# tm7_revD.net
KiCad netlist of a schematic drawn in EAGLE
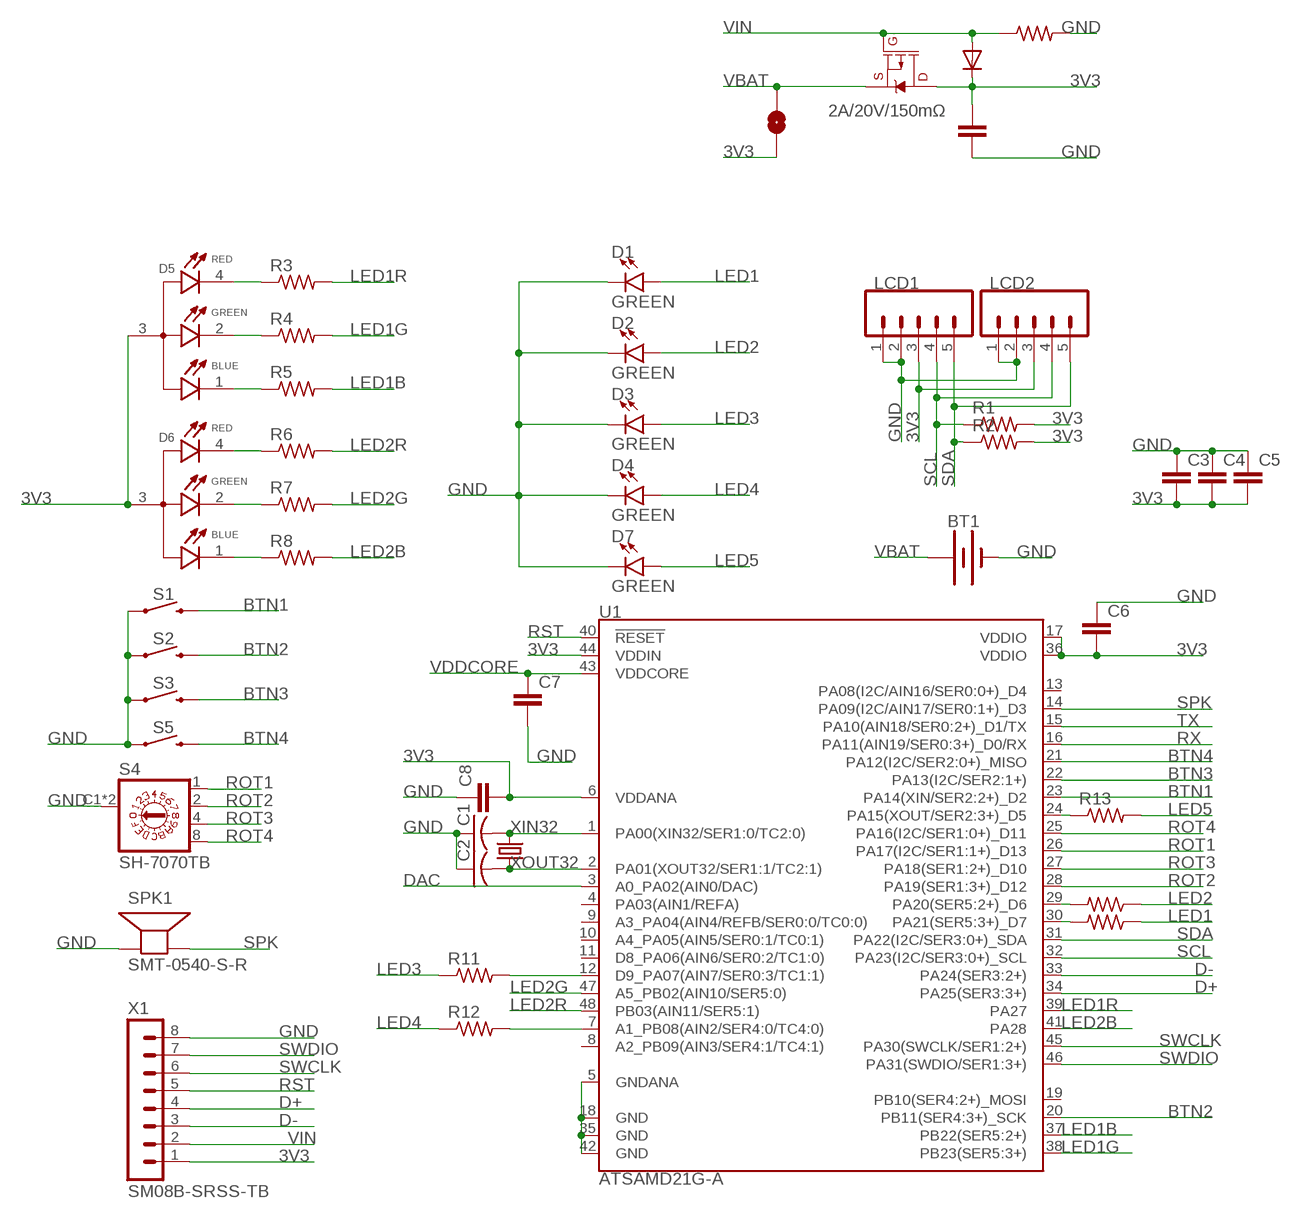
[diagram p0: schematic, sheet 1]

(export (version "E")
  (design (tool "Eeschema 10.0.6"))
  (components
    (comp (ref "BT1")
      (value "BATTERY-20MM_SMD_4LEGS_OVERPASTE_INNER")
      (footprint "eagle-import:BATTCON_20MM_4LEGS_OVERPASTE_INNER")
      (libsource (lib "eagle-import") (part "BATTERY-20MM_SMD_4LEGS_OVERPASTE_INNER"))
    )
    (comp (ref "C1")
      (value "C-USC0603")
      (footprint "eagle-import:C0603")
      (libsource (lib "eagle-import") (part "C-USC0603"))
    )
    (comp (ref "C2")
      (value "C-USC0603")
      (footprint "eagle-import:C0603")
      (libsource (lib "eagle-import") (part "C-USC0603"))
    )
    (comp (ref "C3")
      (value "C-EUC0603")
      (footprint "eagle-import:C0603")
      (libsource (lib "eagle-import") (part "C-EUC0603"))
    )
    (comp (ref "C4")
      (value "C-EUC0603")
      (footprint "eagle-import:C0603")
      (libsource (lib "eagle-import") (part "C-EUC0603"))
    )
    (comp (ref "C5")
      (value "C-EUC0603")
      (footprint "eagle-import:C0603")
      (libsource (lib "eagle-import") (part "C-EUC0603"))
    )
    (comp (ref "C6")
      (value "C-EUC0603")
      (footprint "eagle-import:C0603")
      (libsource (lib "eagle-import") (part "C-EUC0603"))
    )
    (comp (ref "C7")
      (value "C-EUC0603")
      (footprint "eagle-import:C0603")
      (libsource (lib "eagle-import") (part "C-EUC0603"))
    )
    (comp (ref "C8")
      (value "C-EUC0603")
      (footprint "eagle-import:C0603")
      (libsource (lib "eagle-import") (part "C-EUC0603"))
    )
    (comp (ref "C9")
      (value "C-EUC0603")
      (footprint "eagle-import:C0603")
      (libsource (lib "eagle-import") (part "C-EUC0603"))
    )
    (comp (ref "D1")
      (value "GREEN")
      (footprint "eagle-import:LED-1206")
      (libsource (lib "eagle-import") (part "LED-GREEN1206"))
    )
    (comp (ref "D2")
      (value "GREEN")
      (footprint "eagle-import:LED-1206")
      (libsource (lib "eagle-import") (part "LED-GREEN1206"))
    )
    (comp (ref "D3")
      (value "GREEN")
      (footprint "eagle-import:LED-1206")
      (libsource (lib "eagle-import") (part "LED-GREEN1206"))
    )
    (comp (ref "D4")
      (value "GREEN")
      (footprint "eagle-import:LED-1206")
      (libsource (lib "eagle-import") (part "LED-GREEN1206"))
    )
    (comp (ref "D5")
      (value "EAST1616RGBA3")
      (footprint "eagle-import:LED_EAST1616RGBA3")
      (fields (field (name "MF") "Everlight Electronics"))
      (libsource (lib "eagle-import") (part "EAST1616RGBA3"))
    )
    (comp (ref "D6")
      (value "EAST1616RGBA3")
      (footprint "eagle-import:LED_EAST1616RGBA3")
      (fields (field (name "MF") "Everlight Electronics"))
      (libsource (lib "eagle-import") (part "EAST1616RGBA3"))
    )
    (comp (ref "D7")
      (value "GREEN")
      (footprint "eagle-import:LED-1206")
      (libsource (lib "eagle-import") (part "LED-GREEN1206"))
    )
    (comp (ref "D8")
      (value "DIODESOD-323F")
      (footprint "eagle-import:SOD-323F")
      (libsource (lib "eagle-import") (part "DIODESOD-323F"))
    )
    (comp (ref "JP1")
      (value "JUMPER-SMT_2_NO_NO-SILK")
      (footprint "eagle-import:SMT-JUMPER_2_NO_NO-SILK")
      (libsource (lib "eagle-import") (part "JUMPER-SMT_2_NO_NO-SILK"))
    )
    (comp (ref "LCD1")
      (value "CONN_05VERT_FEMALE_HEADER")
      (footprint "eagle-import:1X05_SMD_VERTICAL_COMBO")
      (libsource (lib "eagle-import") (part "CONN_05VERT_FEMALE_HEADER"))
    )
    (comp (ref "LCD2")
      (value "CONN_05VERT_FEMALE_HEADER")
      (footprint "eagle-import:1X05_SMD_VERTICAL_COMBO")
      (libsource (lib "eagle-import") (part "CONN_05VERT_FEMALE_HEADER"))
    )
    (comp (ref "Q1")
      (value "2A/20V/150mΩ")
      (footprint "eagle-import:SOT26")
      (libsource (lib "eagle-import") (part "MOSFET_PCH_DUAL-DMP2240UDM"))
    )
    (comp (ref "R1")
      (value "R-US_R0603")
      (footprint "eagle-import:R0603")
      (libsource (lib "eagle-import") (part "rcl_334_R-US_R0603"))
    )
    (comp (ref "R2")
      (value "R-US_R0603")
      (footprint "eagle-import:R0603")
      (libsource (lib "eagle-import") (part "rcl_334_R-US_R0603"))
    )
    (comp (ref "R3")
      (value "R-US_R0603")
      (footprint "eagle-import:R0603")
      (libsource (lib "eagle-import") (part "rcl_334_R-US_R0603"))
    )
    (comp (ref "R4")
      (value "R-US_R0603")
      (footprint "eagle-import:R0603")
      (libsource (lib "eagle-import") (part "rcl_334_R-US_R0603"))
    )
    (comp (ref "R5")
      (value "R-US_R0603")
      (footprint "eagle-import:R0603")
      (libsource (lib "eagle-import") (part "rcl_334_R-US_R0603"))
    )
    (comp (ref "R6")
      (value "R-US_R0603")
      (footprint "eagle-import:R0603")
      (libsource (lib "eagle-import") (part "rcl_334_R-US_R0603"))
    )
    (comp (ref "R7")
      (value "R-US_R0603")
      (footprint "eagle-import:R0603")
      (libsource (lib "eagle-import") (part "rcl_334_R-US_R0603"))
    )
    (comp (ref "R8")
      (value "R-US_R0603")
      (footprint "eagle-import:R0603")
      (libsource (lib "eagle-import") (part "rcl_334_R-US_R0603"))
    )
    (comp (ref "R9")
      (value "R-US_R0603")
      (footprint "eagle-import:R0603")
      (libsource (lib "eagle-import") (part "rcl_334_R-US_R0603"))
    )
    (comp (ref "R10")
      (value "R-US_R0603")
      (footprint "eagle-import:R0603")
      (libsource (lib "eagle-import") (part "rcl_334_R-US_R0603"))
    )
    (comp (ref "R11")
      (value "R-US_R0603")
      (footprint "eagle-import:R0603")
      (libsource (lib "eagle-import") (part "rcl_334_R-US_R0603"))
    )
    (comp (ref "R12")
      (value "R-US_R0603")
      (footprint "eagle-import:R0603")
      (libsource (lib "eagle-import") (part "rcl_334_R-US_R0603"))
    )
    (comp (ref "R13")
      (value "R-US_R0603")
      (footprint "eagle-import:R0603")
      (libsource (lib "eagle-import") (part "rcl_334_R-US_R0603"))
    )
    (comp (ref "R14")
      (value "R-US_R0603")
      (footprint "eagle-import:R0603")
      (libsource (lib "eagle-import") (part "R-US_R0603"))
    )
    (comp (ref "S1")
      (value "MOMENTARY-SWITCH-SPST-SMD-6.0X3.5MM")
      (footprint "eagle-import:TACTILE_SWITCH_SMD_6.0X3.5MM")
      (libsource (lib "eagle-import") (part "MOMENTARY-SWITCH-SPST-SMD-6.0X3.5MM"))
    )
    (comp (ref "S2")
      (value "MOMENTARY-SWITCH-SPST-SMD-6.0X3.5MM")
      (footprint "eagle-import:TACTILE_SWITCH_SMD_6.0X3.5MM")
      (libsource (lib "eagle-import") (part "MOMENTARY-SWITCH-SPST-SMD-6.0X3.5MM"))
    )
    (comp (ref "S3")
      (value "MOMENTARY-SWITCH-SPST-SMD-6.0X3.5MM")
      (footprint "eagle-import:TACTILE_SWITCH_SMD_6.0X3.5MM")
      (libsource (lib "eagle-import") (part "MOMENTARY-SWITCH-SPST-SMD-6.0X3.5MM"))
    )
    (comp (ref "S4")
      (value "SH-7070TB")
      (footprint "eagle-import:SH-7070B")
      (fields (field (name "MF") "Nidec Copal"))
      (libsource (lib "eagle-import") (part "SH-7070TB"))
    )
    (comp (ref "S5")
      (value "MOMENTARY-SWITCH-SPST-SMD-6.0X3.5MM")
      (footprint "eagle-import:TACTILE_SWITCH_SMD_6.0X3.5MM")
      (libsource (lib "eagle-import") (part "MOMENTARY-SWITCH-SPST-SMD-6.0X3.5MM"))
    )
    (comp (ref "SPK1")
      (value "SMT-0540-S-R")
      (footprint "eagle-import:SMT-0540-S-R")
      (fields (field (name "MF") "PUI"))
      (libsource (lib "eagle-import") (part "SMT-0540-S-R"))
    )
    (comp (ref "U1")
      (value "ATSAMD21G-A")
      (footprint "eagle-import:TQFP-48")
      (libsource (lib "eagle-import") (part "ATSAMD21G-A"))
    )
    (comp (ref "X1")
      (value "SM08B-SRSS-TB")
      (footprint "eagle-import:SM08B-SRSS-TB")
      (libsource (lib "eagle-import") (part "SM08B-SRSS-TB"))
    )
    (comp (ref "Y1")
      (value "32.768kHz")
      (footprint "eagle-import:CRYSTAL-SMD-3.2X1.5MM")
      (libsource (lib "eagle-import") (part "CRYSTAL-32.768KHZSMD-3.2X1.5"))
    )
  )
  (nets
    (net (code "1") (name "/3V3") (class "Default")
      (node (ref "C3") (pin "2") (pinfunction "2_2") (pintype "passive"))
      (node (ref "C4") (pin "2") (pinfunction "2_2") (pintype "passive"))
      (node (ref "C5") (pin "2") (pinfunction "2_2") (pintype "passive"))
      (node (ref "C6") (pin "2") (pinfunction "2_2") (pintype "passive"))
      (node (ref "C8") (pin "2") (pinfunction "2_2") (pintype "passive"))
      (node (ref "C9") (pin "1") (pinfunction "1_1") (pintype "passive"))
      (node (ref "D5") (pin "3") (pinfunction "A_3") (pintype "passive"))
      (node (ref "D6") (pin "3") (pinfunction "A_3") (pintype "passive"))
      (node (ref "D8") (pin "C") (pinfunction "C_C") (pintype "passive"))
      (node (ref "JP1") (pin "1") (pinfunction "1_1") (pintype "passive"))
      (node (ref "LCD1") (pin "3") (pinfunction "3_3") (pintype "passive"))
      (node (ref "LCD2") (pin "3") (pinfunction "3_3") (pintype "passive"))
      (node (ref "Q1") (pin "D1") (pinfunction "D_D1") (pintype "bidirectional"))
      (node (ref "R1") (pin "2") (pinfunction "2_2") (pintype "passive"))
      (node (ref "R2") (pin "2") (pinfunction "2_2") (pintype "passive"))
      (node (ref "U1") (pin "17") (pinfunction "VDDIO_17") (pintype "bidirectional"))
      (node (ref "U1") (pin "36") (pinfunction "VDDIO_36") (pintype "bidirectional"))
      (node (ref "U1") (pin "44") (pinfunction "VDDIN_44") (pintype "bidirectional"))
      (node (ref "U1") (pin "6") (pinfunction "VDDANA_6") (pintype "bidirectional"))
      (node (ref "X1") (pin "1") (pinfunction "1_1") (pintype "passive"))
    )
    (net (code "2") (name "/BTN1") (class "Default")
      (node (ref "S1") (pin "2") (pinfunction "2_2") (pintype "passive"))
      (node (ref "U1") (pin "23") (pinfunction "PA14(XIN/SER2:2+)_D2_23") (pintype "bidirectional"))
    )
    (net (code "3") (name "/BTN2") (class "Default")
      (node (ref "S2") (pin "2") (pinfunction "2_2") (pintype "passive"))
      (node (ref "U1") (pin "20") (pinfunction "PB11(SER4:3+)_SCK_20") (pintype "bidirectional"))
    )
    (net (code "4") (name "/BTN3") (class "Default")
      (node (ref "S3") (pin "2") (pinfunction "2_2") (pintype "passive"))
      (node (ref "U1") (pin "22") (pinfunction "PA13(I2C/SER2:1+)_22") (pintype "bidirectional"))
    )
    (net (code "5") (name "/BTN4") (class "Default")
      (node (ref "S5") (pin "2") (pinfunction "2_2") (pintype "passive"))
      (node (ref "U1") (pin "21") (pinfunction "PA12(I2C/SER2:0+)_MISO_21") (pintype "bidirectional"))
    )
    (net (code "6") (name "/D+") (class "Default")
      (node (ref "U1") (pin "34") (pinfunction "PA25(SER3:3+)_34") (pintype "bidirectional"))
      (node (ref "X1") (pin "4") (pinfunction "4_4") (pintype "passive"))
    )
    (net (code "7") (name "/D-") (class "Default")
      (node (ref "U1") (pin "33") (pinfunction "PA24(SER3:2+)_33") (pintype "bidirectional"))
      (node (ref "X1") (pin "3") (pinfunction "3_3") (pintype "passive"))
    )
    (net (code "8") (name "/DAC") (class "Default")
      (node (ref "U1") (pin "3") (pinfunction "A0_PA02(AIN0/DAC)_3") (pintype "bidirectional"))
    )
    (net (code "9") (name "/GND") (class "Default")
      (node (ref "BT1") (pin "2") (pinfunction "-_2") (pintype "power_in"))
      (node (ref "C1") (pin "1") (pinfunction "1_1") (pintype "passive"))
      (node (ref "C2") (pin "1") (pinfunction "1_1") (pintype "passive"))
      (node (ref "C3") (pin "1") (pinfunction "1_1") (pintype "passive"))
      (node (ref "C4") (pin "1") (pinfunction "1_1") (pintype "passive"))
      (node (ref "C5") (pin "1") (pinfunction "1_1") (pintype "passive"))
      (node (ref "C6") (pin "1") (pinfunction "1_1") (pintype "passive"))
      (node (ref "C7") (pin "2") (pinfunction "2_2") (pintype "passive"))
      (node (ref "C8") (pin "1") (pinfunction "1_1") (pintype "passive"))
      (node (ref "C9") (pin "2") (pinfunction "2_2") (pintype "passive"))
      (node (ref "D1") (pin "C") (pinfunction "C_C") (pintype "passive"))
      (node (ref "D2") (pin "C") (pinfunction "C_C") (pintype "passive"))
      (node (ref "D3") (pin "C") (pinfunction "C_C") (pintype "passive"))
      (node (ref "D4") (pin "C") (pinfunction "C_C") (pintype "passive"))
      (node (ref "D7") (pin "C") (pinfunction "C_C") (pintype "passive"))
      (node (ref "LCD1") (pin "1") (pinfunction "1_1") (pintype "passive"))
      (node (ref "LCD1") (pin "2") (pinfunction "2_2") (pintype "passive"))
      (node (ref "LCD2") (pin "1") (pinfunction "1_1") (pintype "passive"))
      (node (ref "LCD2") (pin "2") (pinfunction "2_2") (pintype "passive"))
      (node (ref "R14") (pin "2") (pinfunction "2_2") (pintype "passive"))
      (node (ref "S1") (pin "1") (pinfunction "1_1") (pintype "passive"))
      (node (ref "S2") (pin "1") (pinfunction "1_1") (pintype "passive"))
      (node (ref "S3") (pin "1") (pinfunction "1_1") (pintype "passive"))
      (node (ref "S4") (pin "C1") (pinfunction "C_C1") (pintype "passive"))
      (node (ref "S4") (pin "C2") (pinfunction "C_C2") (pintype "passive"))
      (node (ref "S5") (pin "1") (pinfunction "1_1") (pintype "passive"))
      (node (ref "SPK1") (pin "-") (pinfunction "+_-") (pintype "passive"))
      (node (ref "U1") (pin "18") (pinfunction "GND_18") (pintype "bidirectional"))
      (node (ref "U1") (pin "35") (pinfunction "GND_35") (pintype "bidirectional"))
      (node (ref "U1") (pin "42") (pinfunction "GND_42") (pintype "bidirectional"))
      (node (ref "U1") (pin "5") (pinfunction "GNDANA_5") (pintype "bidirectional"))
      (node (ref "X1") (pin "8") (pinfunction "8_8") (pintype "passive"))
    )
    (net (code "10") (name "/LED1") (class "Default")
      (node (ref "D1") (pin "A") (pinfunction "A_A") (pintype "passive"))
      (node (ref "R9") (pin "1") (pinfunction "1_1") (pintype "passive"))
    )
    (net (code "11") (name "/LED1B") (class "Default")
      (node (ref "R5") (pin "2") (pinfunction "2_2") (pintype "passive"))
      (node (ref "U1") (pin "37") (pinfunction "PB22(SER5:2+)_37") (pintype "bidirectional"))
    )
    (net (code "12") (name "/LED1G") (class "Default")
      (node (ref "R4") (pin "2") (pinfunction "2_2") (pintype "passive"))
      (node (ref "U1") (pin "38") (pinfunction "PB23(SER5:3+)_38") (pintype "bidirectional"))
    )
    (net (code "13") (name "/LED1R") (class "Default")
      (node (ref "R3") (pin "2") (pinfunction "2_2") (pintype "passive"))
      (node (ref "U1") (pin "39") (pinfunction "PA27_39") (pintype "bidirectional"))
    )
    (net (code "14") (name "/LED2") (class "Default")
      (node (ref "D2") (pin "A") (pinfunction "A_A") (pintype "passive"))
      (node (ref "R10") (pin "1") (pinfunction "1_1") (pintype "passive"))
    )
    (net (code "15") (name "/LED2B") (class "Default")
      (node (ref "R8") (pin "2") (pinfunction "2_2") (pintype "passive"))
      (node (ref "U1") (pin "41") (pinfunction "PA28_41") (pintype "bidirectional"))
    )
    (net (code "16") (name "/LED2G") (class "Default")
      (node (ref "R7") (pin "2") (pinfunction "2_2") (pintype "passive"))
      (node (ref "U1") (pin "47") (pinfunction "A5_PB02(AIN10/SER5:0)_47") (pintype "bidirectional"))
    )
    (net (code "17") (name "/LED2R") (class "Default")
      (node (ref "R6") (pin "2") (pinfunction "2_2") (pintype "passive"))
      (node (ref "U1") (pin "48") (pinfunction "PB03(AIN11/SER5:1)_48") (pintype "bidirectional"))
    )
    (net (code "18") (name "/LED3") (class "Default")
      (node (ref "D3") (pin "A") (pinfunction "A_A") (pintype "passive"))
      (node (ref "R11") (pin "1") (pinfunction "1_1") (pintype "passive"))
    )
    (net (code "19") (name "/LED4") (class "Default")
      (node (ref "D4") (pin "A") (pinfunction "A_A") (pintype "passive"))
      (node (ref "R12") (pin "1") (pinfunction "1_1") (pintype "passive"))
    )
    (net (code "20") (name "/LED5") (class "Default")
      (node (ref "D7") (pin "A") (pinfunction "A_A") (pintype "passive"))
      (node (ref "R13") (pin "2") (pinfunction "2_2") (pintype "passive"))
    )
    (net (code "21") (name "/ROT1") (class "Default")
      (node (ref "S4") (pin "1") (pinfunction "1_1") (pintype "passive"))
      (node (ref "U1") (pin "26") (pinfunction "PA17(I2C/SER1:1+)_D13_26") (pintype "bidirectional"))
    )
    (net (code "22") (name "/ROT2") (class "Default")
      (node (ref "S4") (pin "2") (pinfunction "2_2") (pintype "passive"))
      (node (ref "U1") (pin "28") (pinfunction "PA19(SER1:3+)_D12_28") (pintype "bidirectional"))
    )
    (net (code "23") (name "/ROT3") (class "Default")
      (node (ref "S4") (pin "4") (pinfunction "4_4") (pintype "passive"))
      (node (ref "U1") (pin "27") (pinfunction "PA18(SER1:2+)_D10_27") (pintype "bidirectional"))
    )
    (net (code "24") (name "/ROT4") (class "Default")
      (node (ref "S4") (pin "8") (pinfunction "8_8") (pintype "passive"))
      (node (ref "U1") (pin "25") (pinfunction "PA16(I2C/SER1:0+)_D11_25") (pintype "bidirectional"))
    )
    (net (code "25") (name "/RST") (class "Default")
      (node (ref "U1") (pin "40") (pinfunction "~{RESET}_40") (pintype "bidirectional"))
      (node (ref "X1") (pin "5") (pinfunction "5_5") (pintype "passive"))
    )
    (net (code "26") (name "/RX") (class "Default")
      (node (ref "U1") (pin "16") (pinfunction "PA11(AIN19/SER0:3+)_D0/RX_16") (pintype "bidirectional"))
    )
    (net (code "27") (name "/SCL") (class "Default")
      (node (ref "LCD1") (pin "4") (pinfunction "4_4") (pintype "passive"))
      (node (ref "LCD2") (pin "4") (pinfunction "4_4") (pintype "passive"))
      (node (ref "R1") (pin "1") (pinfunction "1_1") (pintype "passive"))
      (node (ref "U1") (pin "32") (pinfunction "PA23(I2C/SER3:0+)_SCL_32") (pintype "bidirectional"))
    )
    (net (code "28") (name "/SDA") (class "Default")
      (node (ref "LCD1") (pin "5") (pinfunction "5_5") (pintype "passive"))
      (node (ref "LCD2") (pin "5") (pinfunction "5_5") (pintype "passive"))
      (node (ref "R2") (pin "1") (pinfunction "1_1") (pintype "passive"))
      (node (ref "U1") (pin "31") (pinfunction "PA22(I2C/SER3:0+)_SDA_31") (pintype "bidirectional"))
    )
    (net (code "29") (name "/SPK") (class "Default")
      (node (ref "SPK1") (pin "+") (pinfunction "-_+") (pintype "passive"))
      (node (ref "U1") (pin "14") (pinfunction "PA09(I2C/AIN17/SER0:1+)_D3_14") (pintype "bidirectional"))
    )
    (net (code "30") (name "/SWCLK") (class "Default")
      (node (ref "U1") (pin "45") (pinfunction "PA30(SWCLK/SER1:2+)_45") (pintype "bidirectional"))
      (node (ref "X1") (pin "6") (pinfunction "6_6") (pintype "passive"))
    )
    (net (code "31") (name "/SWDIO") (class "Default")
      (node (ref "U1") (pin "46") (pinfunction "PA31(SWDIO/SER1:3+)_46") (pintype "bidirectional"))
      (node (ref "X1") (pin "7") (pinfunction "7_7") (pintype "passive"))
    )
    (net (code "32") (name "/TX") (class "Default")
      (node (ref "U1") (pin "15") (pinfunction "PA10(AIN18/SER0:2+)_D1/TX_15") (pintype "bidirectional"))
    )
    (net (code "33") (name "/VBAT") (class "Default")
      (node (ref "BT1") (pin "1") (pinfunction "+_1") (pintype "power_in"))
      (node (ref "JP1") (pin "2") (pinfunction "2_2") (pintype "passive"))
      (node (ref "Q1") (pin "S1") (pinfunction "S_S1") (pintype "bidirectional"))
    )
    (net (code "34") (name "/VDDCORE") (class "Default")
      (node (ref "C7") (pin "1") (pinfunction "1_1") (pintype "passive"))
      (node (ref "U1") (pin "43") (pinfunction "VDDCORE_43") (pintype "bidirectional"))
    )
    (net (code "35") (name "/VIN") (class "Default")
      (node (ref "D8") (pin "A") (pinfunction "A_A") (pintype "passive"))
      (node (ref "Q1") (pin "G1") (pinfunction "G_G1") (pintype "bidirectional"))
      (node (ref "R14") (pin "1") (pinfunction "1_1") (pintype "passive"))
      (node (ref "X1") (pin "2") (pinfunction "2_2") (pintype "passive"))
    )
    (net (code "36") (name "/XIN32") (class "Default")
      (node (ref "C1") (pin "2") (pinfunction "2_2") (pintype "passive"))
      (node (ref "U1") (pin "1") (pinfunction "PA00(XIN32/SER1:0/TC2:0)_1") (pintype "bidirectional"))
      (node (ref "Y1") (pin "P$2") (pinfunction "2_P$2") (pintype "passive"))
    )
    (net (code "37") (name "/XOUT32") (class "Default")
      (node (ref "C2") (pin "2") (pinfunction "2_2") (pintype "passive"))
      (node (ref "U1") (pin "2") (pinfunction "PA01(XOUT32/SER1:1/TC2:1)_2") (pintype "bidirectional"))
      (node (ref "Y1") (pin "P$1") (pinfunction "1_P$1") (pintype "passive"))
    )
    (net (code "38") (name "Net-(D5-B_C)") (class "Default")
      (node (ref "D5") (pin "1") (pinfunction "B_C_1") (pintype "passive"))
      (node (ref "R5") (pin "1") (pinfunction "1_1") (pintype "passive"))
    )
    (net (code "39") (name "Net-(D5-G_C)") (class "Default")
      (node (ref "D5") (pin "2") (pinfunction "G_C_2") (pintype "passive"))
      (node (ref "R4") (pin "1") (pinfunction "1_1") (pintype "passive"))
    )
    (net (code "40") (name "Net-(D5-R_C)") (class "Default")
      (node (ref "D5") (pin "4") (pinfunction "R_C_4") (pintype "passive"))
      (node (ref "R3") (pin "1") (pinfunction "1_1") (pintype "passive"))
    )
    (net (code "41") (name "Net-(D6-B_C)") (class "Default")
      (node (ref "D6") (pin "1") (pinfunction "B_C_1") (pintype "passive"))
      (node (ref "R8") (pin "1") (pinfunction "1_1") (pintype "passive"))
    )
    (net (code "42") (name "Net-(D6-G_C)") (class "Default")
      (node (ref "D6") (pin "2") (pinfunction "G_C_2") (pintype "passive"))
      (node (ref "R7") (pin "1") (pinfunction "1_1") (pintype "passive"))
    )
    (net (code "43") (name "Net-(D6-R_C)") (class "Default")
      (node (ref "D6") (pin "4") (pinfunction "R_C_4") (pintype "passive"))
      (node (ref "R6") (pin "1") (pinfunction "1_1") (pintype "passive"))
    )
    (net (code "44") (name "Net-(U1-A1_PB08(AIN2{slash}SER4:0{slash}TC4:0))") (class "Default")
      (node (ref "R12") (pin "2") (pinfunction "2_2") (pintype "passive"))
      (node (ref "U1") (pin "7") (pinfunction "A1_PB08(AIN2/SER4:0/TC4:0)_7") (pintype "bidirectional"))
    )
    (net (code "45") (name "Net-(U1-D9_PA07(AIN7{slash}SER0:3{slash}TC1:1))") (class "Default")
      (node (ref "R11") (pin "2") (pinfunction "2_2") (pintype "passive"))
      (node (ref "U1") (pin "12") (pinfunction "D9_PA07(AIN7/SER0:3/TC1:1)_12") (pintype "bidirectional"))
    )
    (net (code "46") (name "Net-(U1-PA15(XOUT{slash}SER2:3+)_D5)") (class "Default")
      (node (ref "R13") (pin "1") (pinfunction "1_1") (pintype "passive"))
      (node (ref "U1") (pin "24") (pinfunction "PA15(XOUT/SER2:3+)_D5_24") (pintype "bidirectional"))
    )
    (net (code "47") (name "Net-(U1-PA20(SER5:2+)_D6)") (class "Default")
      (node (ref "R10") (pin "2") (pinfunction "2_2") (pintype "passive"))
      (node (ref "U1") (pin "29") (pinfunction "PA20(SER5:2+)_D6_29") (pintype "bidirectional"))
    )
    (net (code "48") (name "Net-(U1-PA21(SER5:3+)_D7)") (class "Default")
      (node (ref "R9") (pin "2") (pinfunction "2_2") (pintype "passive"))
      (node (ref "U1") (pin "30") (pinfunction "PA21(SER5:3+)_D7_30") (pintype "bidirectional"))
    )
    (net (code "49") (name "unconnected-(U1-A2_PB09(AIN3{slash}SER4:1{slash}TC4:1)-Pad8)") (class "Default")
      (node (ref "U1") (pin "8") (pinfunction "A2_PB09(AIN3/SER4:1/TC4:1)_8") (pintype "bidirectional"))
    )
    (net (code "50") (name "unconnected-(U1-A3_PA04(AIN4{slash}REFB{slash}SER0:0{slash}TC0:0)-Pad9)") (class "Default")
      (node (ref "U1") (pin "9") (pinfunction "A3_PA04(AIN4/REFB/SER0:0/TC0:0)_9") (pintype "bidirectional"))
    )
    (net (code "51") (name "unconnected-(U1-A4_PA05(AIN5{slash}SER0:1{slash}TC0:1)-Pad10)") (class "Default")
      (node (ref "U1") (pin "10") (pinfunction "A4_PA05(AIN5/SER0:1/TC0:1)_10") (pintype "bidirectional"))
    )
    (net (code "52") (name "unconnected-(U1-D8_PA06(AIN6{slash}SER0:2{slash}TC1:0)-Pad11)") (class "Default")
      (node (ref "U1") (pin "11") (pinfunction "D8_PA06(AIN6/SER0:2/TC1:0)_11") (pintype "bidirectional"))
    )
    (net (code "53") (name "unconnected-(U1-PA03(AIN1{slash}REFA)-Pad4)") (class "Default")
      (node (ref "U1") (pin "4") (pinfunction "PA03(AIN1/REFA)_4") (pintype "bidirectional"))
    )
    (net (code "54") (name "unconnected-(U1-PA08(I2C{slash}AIN16{slash}SER0:0+)_D4-Pad13)") (class "Default")
      (node (ref "U1") (pin "13") (pinfunction "PA08(I2C/AIN16/SER0:0+)_D4_13") (pintype "bidirectional"))
    )
    (net (code "55") (name "unconnected-(U1-PB10(SER4:2+)_MOSI-Pad19)") (class "Default")
      (node (ref "U1") (pin "19") (pinfunction "PB10(SER4:2+)_MOSI_19") (pintype "bidirectional"))
    )
  )
)
